# SensorBoard.net
KiCad netlist of a schematic drawn in EAGLE
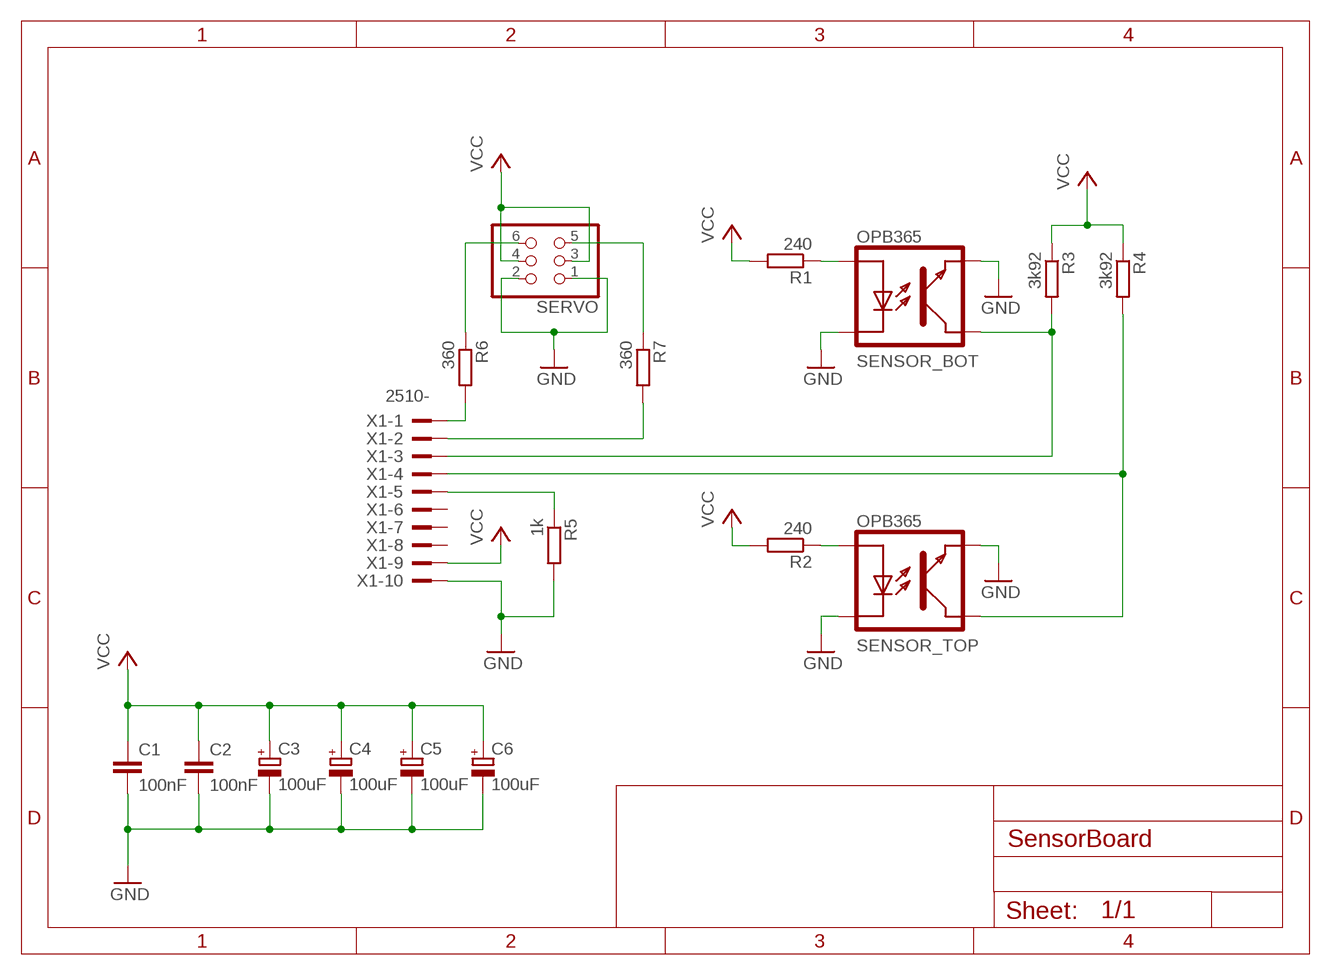
[diagram p0: schematic, sheet 1]

(export (version "E")
  (design (tool "Eeschema 10.0.6"))
  (components
    (comp (ref "C1")
      (value "100nF")
      (footprint "eagle-import:C1206")
      (libsource (lib "eagle-import") (part "C-EUC1206"))
    )
    (comp (ref "C2")
      (value "100nF")
      (footprint "eagle-import:C1206")
      (libsource (lib "eagle-import") (part "C-EUC1206"))
    )
    (comp (ref "C3")
      (value "100uF")
      (footprint "eagle-import:SMC_D")
      (libsource (lib "eagle-import") (part "CPOL-EUSMCD"))
    )
    (comp (ref "C4")
      (value "100uF")
      (footprint "eagle-import:SMC_D")
      (libsource (lib "eagle-import") (part "CPOL-EUSMCD"))
    )
    (comp (ref "C5")
      (value "100uF")
      (footprint "eagle-import:SMC_D")
      (libsource (lib "eagle-import") (part "CPOL-EUSMCD"))
    )
    (comp (ref "C6")
      (value "100uF")
      (footprint "eagle-import:SMC_D")
      (libsource (lib "eagle-import") (part "CPOL-EUSMCD"))
    )
    (comp (ref "R1")
      (value "240")
      (footprint "eagle-import:R1206")
      (libsource (lib "eagle-import") (part "R-EU_R1206"))
    )
    (comp (ref "R2")
      (value "240")
      (footprint "eagle-import:R1206")
      (libsource (lib "eagle-import") (part "R-EU_R1206"))
    )
    (comp (ref "R3")
      (value "3k92")
      (footprint "eagle-import:R1206")
      (libsource (lib "eagle-import") (part "R-EU_R1206"))
    )
    (comp (ref "R4")
      (value "3k92")
      (footprint "eagle-import:R1206")
      (libsource (lib "eagle-import") (part "R-EU_R1206"))
    )
    (comp (ref "R5")
      (value "1k")
      (footprint "eagle-import:R1206")
      (libsource (lib "eagle-import") (part "R-EU_R1206"))
    )
    (comp (ref "R6")
      (value "360")
      (footprint "eagle-import:R1206")
      (libsource (lib "eagle-import") (part "R-EU_R1206"))
    )
    (comp (ref "R7")
      (value "360")
      (footprint "eagle-import:R1206")
      (libsource (lib "eagle-import") (part "R-EU_R1206"))
    )
    (comp (ref "SENSOR_BOT")
      (value "OPB365T")
      (footprint "eagle-import:OPB365-T")
      (libsource (lib "eagle-import") (part "OPB365T"))
    )
    (comp (ref "SENSOR_TOP")
      (value "OPB365T")
      (footprint "eagle-import:OPB365-T")
      (libsource (lib "eagle-import") (part "OPB365T"))
    )
    (comp (ref "SERVO")
      (value "PINHD-2X3/90")
      (footprint "eagle-import:2X03_90")
      (libsource (lib "eagle-import") (part "PINHD-2X3/90"))
    )
    (comp (ref "X1")
      (value "2510-")
      (footprint "eagle-import:PAK100_2500-10")
      (fields (field (name "MF") "3M") (field (name "MPN") "2510-6002UB"))
      (libsource (lib "eagle-import") (part "2510-"))
    )
  )
  (nets
    (net (code "1") (name "GND") (class "Default")
      (node (ref "C1") (pin "2") (pinfunction "2_2") (pintype "passive"))
      (node (ref "C2") (pin "2") (pinfunction "2_2") (pintype "passive"))
      (node (ref "C3") (pin "-") (pinfunction "-_-") (pintype "passive"))
      (node (ref "C4") (pin "-") (pinfunction "-_-") (pintype "passive"))
      (node (ref "C5") (pin "-") (pinfunction "-_-") (pintype "passive"))
      (node (ref "C6") (pin "-") (pinfunction "-_-") (pintype "passive"))
      (node (ref "R5") (pin "2") (pinfunction "2_2") (pintype "passive"))
      (node (ref "SENSOR_BOT") (pin "2") (pinfunction "2_2") (pintype "bidirectional"))
      (node (ref "SENSOR_BOT") (pin "4") (pinfunction "4_4") (pintype "bidirectional"))
      (node (ref "SENSOR_TOP") (pin "2") (pinfunction "2_2") (pintype "bidirectional"))
      (node (ref "SENSOR_TOP") (pin "4") (pinfunction "4_4") (pintype "bidirectional"))
      (node (ref "SERVO") (pin "1") (pinfunction "1_1") (pintype "passive"))
      (node (ref "SERVO") (pin "2") (pinfunction "2_2") (pintype "passive"))
      (node (ref "X1") (pin "10") (pinfunction "KL_10") (pintype "passive"))
    )
    (net (code "2") (name "Net-(R1-Pad1)") (class "Default")
      (node (ref "R1") (pin "1") (pinfunction "1_1") (pintype "passive"))
      (node (ref "SENSOR_BOT") (pin "1") (pinfunction "1_1") (pintype "bidirectional"))
    )
    (net (code "3") (name "Net-(R2-Pad1)") (class "Default")
      (node (ref "R2") (pin "1") (pinfunction "1_1") (pintype "passive"))
      (node (ref "SENSOR_TOP") (pin "1") (pinfunction "1_1") (pintype "bidirectional"))
    )
    (net (code "4") (name "Net-(R6-Pad1)") (class "Default")
      (node (ref "R6") (pin "1") (pinfunction "1_1") (pintype "passive"))
      (node (ref "SERVO") (pin "6") (pinfunction "6_6") (pintype "passive"))
    )
    (net (code "5") (name "Net-(R7-Pad1)") (class "Default")
      (node (ref "R7") (pin "1") (pinfunction "1_1") (pintype "passive"))
      (node (ref "SERVO") (pin "5") (pinfunction "5_5") (pintype "passive"))
    )
    (net (code "6") (name "Net-(X1A-KL)") (class "Default")
      (node (ref "R6") (pin "2") (pinfunction "2_2") (pintype "passive"))
      (node (ref "X1") (pin "1") (pinfunction "KL_1") (pintype "passive"))
    )
    (net (code "7") (name "Net-(X1C-KL)") (class "Default")
      (node (ref "R7") (pin "2") (pinfunction "2_2") (pintype "passive"))
      (node (ref "X1") (pin "2") (pinfunction "KL_2") (pintype "passive"))
    )
    (net (code "8") (name "Net-(X1D-KL)") (class "Default")
      (node (ref "R3") (pin "2") (pinfunction "2_2") (pintype "passive"))
      (node (ref "SENSOR_BOT") (pin "3") (pinfunction "3_3") (pintype "bidirectional"))
      (node (ref "X1") (pin "3") (pinfunction "KL_3") (pintype "passive"))
    )
    (net (code "9") (name "Net-(X1E-KL)") (class "Default")
      (node (ref "R4") (pin "2") (pinfunction "2_2") (pintype "passive"))
      (node (ref "SENSOR_TOP") (pin "3") (pinfunction "3_3") (pintype "bidirectional"))
      (node (ref "X1") (pin "4") (pinfunction "KL_4") (pintype "passive"))
    )
    (net (code "10") (name "Net-(X1F-KL)") (class "Default")
      (node (ref "R5") (pin "1") (pinfunction "1_1") (pintype "passive"))
      (node (ref "X1") (pin "5") (pinfunction "KL_5") (pintype "passive"))
    )
    (net (code "11") (name "VCC") (class "Default")
      (node (ref "C1") (pin "1") (pinfunction "1_1") (pintype "passive"))
      (node (ref "C2") (pin "1") (pinfunction "1_1") (pintype "passive"))
      (node (ref "C3") (pin "+") (pinfunction "+_+") (pintype "passive"))
      (node (ref "C4") (pin "+") (pinfunction "+_+") (pintype "passive"))
      (node (ref "C5") (pin "+") (pinfunction "+_+") (pintype "passive"))
      (node (ref "C6") (pin "+") (pinfunction "+_+") (pintype "passive"))
      (node (ref "R1") (pin "2") (pinfunction "2_2") (pintype "passive"))
      (node (ref "R2") (pin "2") (pinfunction "2_2") (pintype "passive"))
      (node (ref "R3") (pin "1") (pinfunction "1_1") (pintype "passive"))
      (node (ref "R4") (pin "1") (pinfunction "1_1") (pintype "passive"))
      (node (ref "SERVO") (pin "3") (pinfunction "3_3") (pintype "passive"))
      (node (ref "SERVO") (pin "4") (pinfunction "4_4") (pintype "passive"))
      (node (ref "X1") (pin "9") (pinfunction "KL_9") (pintype "passive"))
    )
    (net (code "12") (name "unconnected-(X1G-KL-Pad6)") (class "Default")
      (node (ref "X1") (pin "6") (pinfunction "KL_6") (pintype "passive"))
    )
    (net (code "13") (name "unconnected-(X1H-KL-Pad7)") (class "Default")
      (node (ref "X1") (pin "7") (pinfunction "KL_7") (pintype "passive"))
    )
    (net (code "14") (name "unconnected-(X1I-KL-Pad8)") (class "Default")
      (node (ref "X1") (pin "8") (pinfunction "KL_8") (pintype "passive"))
    )
  )
)
